# LabPower-PWM.net
KiCad netlist of a schematic drawn in EAGLE
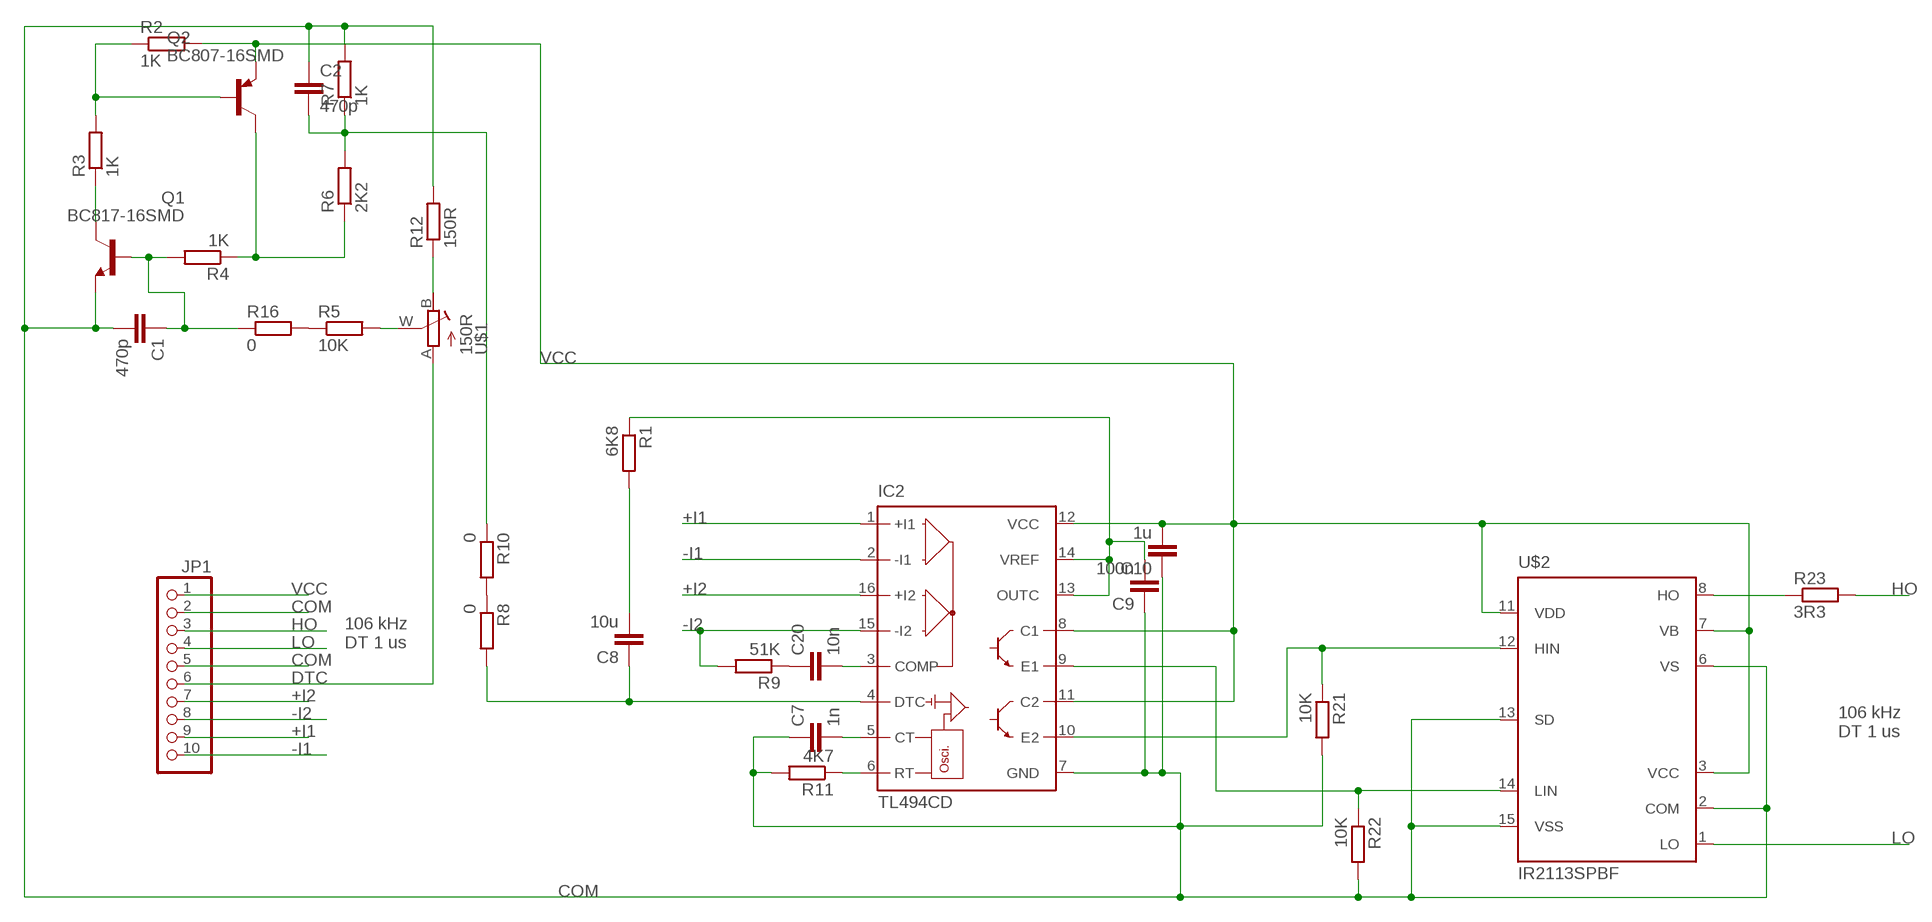
[diagram p0: schematic, sheet 1]

(export (version "E")
  (design (tool "Eeschema 10.0.6"))
  (components
    (comp (ref "C1")
      (value "470p")
      (footprint "eagle-import:C0805")
      (libsource (lib "eagle-import") (part "C-EUC0805"))
    )
    (comp (ref "C2")
      (value "470p")
      (footprint "eagle-import:C0805")
      (libsource (lib "eagle-import") (part "C-EUC0805"))
    )
    (comp (ref "C7")
      (value "1n")
      (footprint "eagle-import:C0805")
      (libsource (lib "eagle-import") (part "C-EUC0805"))
    )
    (comp (ref "C8")
      (value "10u")
      (footprint "eagle-import:C0805")
      (libsource (lib "eagle-import") (part "C-EUC0805"))
    )
    (comp (ref "C9")
      (value "100n")
      (footprint "eagle-import:C0805")
      (libsource (lib "eagle-import") (part "C-EUC0805"))
    )
    (comp (ref "C10")
      (value "1u")
      (footprint "eagle-import:C0805")
      (libsource (lib "eagle-import") (part "C-EUC0805"))
    )
    (comp (ref "C20")
      (value "10n")
      (footprint "eagle-import:C0805")
      (libsource (lib "eagle-import") (part "C-EUC0805"))
    )
    (comp (ref "IC2")
      (value "TL494CD")
      (footprint "eagle-import:SO16")
      (libsource (lib "eagle-import") (part "TL494DC"))
    )
    (comp (ref "JP1")
      (value "PINHD-1X10")
      (footprint "eagle-import:1X10")
      (libsource (lib "eagle-import") (part "PINHD-1X10"))
    )
    (comp (ref "Q1")
      (value "BC817-16SMD")
      (footprint "eagle-import:SOT23-BEC")
      (libsource (lib "eagle-import") (part "BC817SMD-16"))
    )
    (comp (ref "Q2")
      (value "BC807-16SMD")
      (footprint "eagle-import:SOT23-BEC")
      (libsource (lib "eagle-import") (part "BC807SMD-16"))
    )
    (comp (ref "R1")
      (value "6K8")
      (footprint "eagle-import:R0805")
      (libsource (lib "eagle-import") (part "R-EU_R0805"))
    )
    (comp (ref "R2")
      (value "1K")
      (footprint "eagle-import:R0805")
      (libsource (lib "eagle-import") (part "R-EU_R0805"))
    )
    (comp (ref "R3")
      (value "1K")
      (footprint "eagle-import:R0805")
      (libsource (lib "eagle-import") (part "R-EU_R0805"))
    )
    (comp (ref "R4")
      (value "1K")
      (footprint "eagle-import:R0805")
      (libsource (lib "eagle-import") (part "R-EU_R0805"))
    )
    (comp (ref "R5")
      (value "10K")
      (footprint "eagle-import:R0805")
      (libsource (lib "eagle-import") (part "R-EU_R0805"))
    )
    (comp (ref "R6")
      (value "2K2")
      (footprint "eagle-import:R0805")
      (libsource (lib "eagle-import") (part "R-EU_R0805"))
    )
    (comp (ref "R7")
      (value "1K")
      (footprint "eagle-import:R0805")
      (libsource (lib "eagle-import") (part "R-EU_R0805"))
    )
    (comp (ref "R8")
      (value "0")
      (footprint "eagle-import:R0805")
      (libsource (lib "eagle-import") (part "R-EU_R0805"))
    )
    (comp (ref "R9")
      (value "51K")
      (footprint "eagle-import:R0805")
      (libsource (lib "eagle-import") (part "R-EU_R0805"))
    )
    (comp (ref "R10")
      (value "0")
      (footprint "eagle-import:R0805")
      (libsource (lib "eagle-import") (part "R-EU_R0805"))
    )
    (comp (ref "R11")
      (value "4K7")
      (footprint "eagle-import:R0805")
      (libsource (lib "eagle-import") (part "R-EU_R0805"))
    )
    (comp (ref "R12")
      (value "150R")
      (footprint "eagle-import:R0805")
      (libsource (lib "eagle-import") (part "R-EU_R0805"))
    )
    (comp (ref "R16")
      (value "0")
      (footprint "eagle-import:R0805")
      (libsource (lib "eagle-import") (part "R-EU_R0805"))
    )
    (comp (ref "R21")
      (value "10K")
      (footprint "eagle-import:R0805")
      (libsource (lib "eagle-import") (part "R-EU_R0805"))
    )
    (comp (ref "R22")
      (value "10K")
      (footprint "eagle-import:R0805")
      (libsource (lib "eagle-import") (part "R-EU_R0805"))
    )
    (comp (ref "R23")
      (value "3R3")
      (footprint "eagle-import:R0805")
      (libsource (lib "eagle-import") (part "R-EU_R0805"))
    )
    (comp (ref "U$1")
      (value "150R")
      (footprint "eagle-import:RJ9W")
      (libsource (lib "eagle-import") (part "POTTURN-X"))
    )
    (comp (ref "U$2")
      (value "IR2113SPBF")
      (footprint "eagle-import:SO16W")
      (libsource (lib "eagle-import") (part "IR2113SPBF"))
    )
  )
  (nets
    (net (code "1") (name "/+I1") (class "Default")
      (node (ref "IC2") (pin "1") (pinfunction "+I1_1") (pintype "input"))
      (node (ref "JP1") (pin "9") (pinfunction "9_9") (pintype "passive"))
    )
    (net (code "2") (name "/+I2") (class "Default")
      (node (ref "IC2") (pin "16") (pinfunction "+I2_16") (pintype "input"))
      (node (ref "JP1") (pin "7") (pinfunction "7_7") (pintype "passive"))
    )
    (net (code "3") (name "/-I1") (class "Default")
      (node (ref "IC2") (pin "2") (pinfunction "-I1_2") (pintype "input"))
      (node (ref "JP1") (pin "10") (pinfunction "10_10") (pintype "passive"))
    )
    (net (code "4") (name "/-I2") (class "Default")
      (node (ref "IC2") (pin "15") (pinfunction "-I2_15") (pintype "input"))
      (node (ref "JP1") (pin "8") (pinfunction "8_8") (pintype "passive"))
      (node (ref "R9") (pin "2") (pinfunction "2_2") (pintype "passive"))
    )
    (net (code "5") (name "/COM") (class "Default")
      (node (ref "C1") (pin "2") (pinfunction "2_2") (pintype "passive"))
      (node (ref "C10") (pin "1") (pinfunction "1_1") (pintype "passive"))
      (node (ref "C2") (pin "1") (pinfunction "1_1") (pintype "passive"))
      (node (ref "C7") (pin "1") (pinfunction "1_1") (pintype "passive"))
      (node (ref "C9") (pin "1") (pinfunction "1_1") (pintype "passive"))
      (node (ref "IC2") (pin "7") (pinfunction "GND_7") (pintype "power_in"))
      (node (ref "JP1") (pin "2") (pinfunction "2_2") (pintype "passive"))
      (node (ref "JP1") (pin "5") (pinfunction "5_5") (pintype "passive"))
      (node (ref "Q1") (pin "E") (pinfunction "E_E") (pintype "passive"))
      (node (ref "R11") (pin "2") (pinfunction "2_2") (pintype "passive"))
      (node (ref "R12") (pin "2") (pinfunction "2_2") (pintype "passive"))
      (node (ref "R21") (pin "2") (pinfunction "2_2") (pintype "passive"))
      (node (ref "R22") (pin "2") (pinfunction "2_2") (pintype "passive"))
      (node (ref "R7") (pin "2") (pinfunction "2_2") (pintype "passive"))
      (node (ref "U$2") (pin "13") (pinfunction "SD_13") (pintype "input"))
      (node (ref "U$2") (pin "15") (pinfunction "VSS_15") (pintype "power_in"))
      (node (ref "U$2") (pin "2") (pinfunction "COM_2") (pintype "power_in"))
      (node (ref "U$2") (pin "6") (pinfunction "VS_6") (pintype "power_in"))
    )
    (net (code "6") (name "/DTC") (class "Default")
      (node (ref "JP1") (pin "6") (pinfunction "6_6") (pintype "passive"))
      (node (ref "U$1") (pin "A") (pinfunction "A_A") (pintype "passive"))
    )
    (net (code "7") (name "/HO") (class "Default")
      (node (ref "JP1") (pin "3") (pinfunction "3_3") (pintype "passive"))
      (node (ref "R23") (pin "2") (pinfunction "2_2") (pintype "passive"))
    )
    (net (code "8") (name "/LO") (class "Default")
      (node (ref "JP1") (pin "4") (pinfunction "4_4") (pintype "passive"))
      (node (ref "U$2") (pin "1") (pinfunction "LO_1") (pintype "output"))
    )
    (net (code "9") (name "/VCC") (class "Default")
      (node (ref "C10") (pin "2") (pinfunction "2_2") (pintype "passive"))
      (node (ref "IC2") (pin "11") (pinfunction "C2_11") (pintype "passive"))
      (node (ref "IC2") (pin "12") (pinfunction "VCC_12") (pintype "power_in"))
      (node (ref "IC2") (pin "8") (pinfunction "C1_8") (pintype "passive"))
      (node (ref "JP1") (pin "1") (pinfunction "1_1") (pintype "passive"))
      (node (ref "Q2") (pin "E") (pinfunction "E_E") (pintype "passive"))
      (node (ref "R2") (pin "2") (pinfunction "2_2") (pintype "passive"))
      (node (ref "U$2") (pin "11") (pinfunction "VDD_11") (pintype "power_in"))
      (node (ref "U$2") (pin "3") (pinfunction "VCC_3") (pintype "power_in"))
      (node (ref "U$2") (pin "7") (pinfunction "VB_7") (pintype "power_in"))
    )
    (net (code "10") (name "Net-(C1-Pad1)") (class "Default")
      (node (ref "C1") (pin "1") (pinfunction "1_1") (pintype "passive"))
      (node (ref "Q1") (pin "B") (pinfunction "B_B") (pintype "passive"))
      (node (ref "R16") (pin "1") (pinfunction "1_1") (pintype "passive"))
      (node (ref "R4") (pin "2") (pinfunction "2_2") (pintype "passive"))
    )
    (net (code "11") (name "Net-(C2-Pad2)") (class "Default")
      (node (ref "C2") (pin "2") (pinfunction "2_2") (pintype "passive"))
      (node (ref "R10") (pin "1") (pinfunction "1_1") (pintype "passive"))
      (node (ref "R6") (pin "2") (pinfunction "2_2") (pintype "passive"))
      (node (ref "R7") (pin "1") (pinfunction "1_1") (pintype "passive"))
    )
    (net (code "12") (name "Net-(C8-Pad2)") (class "Default")
      (node (ref "C8") (pin "2") (pinfunction "2_2") (pintype "passive"))
      (node (ref "R1") (pin "2") (pinfunction "2_2") (pintype "passive"))
    )
    (net (code "13") (name "Net-(C20-Pad1)") (class "Default")
      (node (ref "C20") (pin "1") (pinfunction "1_1") (pintype "passive"))
      (node (ref "R9") (pin "1") (pinfunction "1_1") (pintype "passive"))
    )
    (net (code "14") (name "Net-(IC2-COMP)") (class "Default")
      (node (ref "C20") (pin "2") (pinfunction "2_2") (pintype "passive"))
      (node (ref "IC2") (pin "3") (pinfunction "COMP_3") (pintype "passive"))
    )
    (net (code "15") (name "Net-(IC2-CT)") (class "Default")
      (node (ref "C7") (pin "2") (pinfunction "2_2") (pintype "passive"))
      (node (ref "IC2") (pin "5") (pinfunction "CT_5") (pintype "input"))
    )
    (net (code "16") (name "Net-(IC2-DTC)") (class "Default")
      (node (ref "C8") (pin "1") (pinfunction "1_1") (pintype "passive"))
      (node (ref "IC2") (pin "4") (pinfunction "DTC_4") (pintype "input"))
      (node (ref "R8") (pin "2") (pinfunction "2_2") (pintype "passive"))
    )
    (net (code "17") (name "Net-(IC2-E1)") (class "Default")
      (node (ref "IC2") (pin "9") (pinfunction "E1_9") (pintype "passive"))
      (node (ref "R22") (pin "1") (pinfunction "1_1") (pintype "passive"))
      (node (ref "U$2") (pin "14") (pinfunction "LIN_14") (pintype "input"))
    )
    (net (code "18") (name "Net-(IC2-E2)") (class "Default")
      (node (ref "IC2") (pin "10") (pinfunction "E2_10") (pintype "passive"))
      (node (ref "R21") (pin "1") (pinfunction "1_1") (pintype "passive"))
      (node (ref "U$2") (pin "12") (pinfunction "HIN_12") (pintype "input"))
    )
    (net (code "19") (name "Net-(IC2-OUTC)") (class "Default")
      (node (ref "C9") (pin "2") (pinfunction "2_2") (pintype "passive"))
      (node (ref "IC2") (pin "13") (pinfunction "OUTC_13") (pintype "output"))
      (node (ref "IC2") (pin "14") (pinfunction "VREF_14") (pintype "input"))
      (node (ref "R1") (pin "1") (pinfunction "1_1") (pintype "passive"))
    )
    (net (code "20") (name "Net-(IC2-RT)") (class "Default")
      (node (ref "IC2") (pin "6") (pinfunction "RT_6") (pintype "input"))
      (node (ref "R11") (pin "1") (pinfunction "1_1") (pintype "passive"))
    )
    (net (code "21") (name "Net-(Q1-PadC)") (class "Default")
      (node (ref "Q1") (pin "C") (pinfunction "C_C") (pintype "passive"))
      (node (ref "R3") (pin "1") (pinfunction "1_1") (pintype "passive"))
    )
    (net (code "22") (name "Net-(Q2-PadB)") (class "Default")
      (node (ref "Q2") (pin "B") (pinfunction "B_B") (pintype "passive"))
      (node (ref "R2") (pin "1") (pinfunction "1_1") (pintype "passive"))
      (node (ref "R3") (pin "2") (pinfunction "2_2") (pintype "passive"))
    )
    (net (code "23") (name "Net-(Q2-PadC)") (class "Default")
      (node (ref "Q2") (pin "C") (pinfunction "C_C") (pintype "passive"))
      (node (ref "R4") (pin "1") (pinfunction "1_1") (pintype "passive"))
      (node (ref "R6") (pin "1") (pinfunction "1_1") (pintype "passive"))
    )
    (net (code "24") (name "Net-(R10-Pad2)") (class "Default")
      (node (ref "R10") (pin "2") (pinfunction "2_2") (pintype "passive"))
      (node (ref "R8") (pin "1") (pinfunction "1_1") (pintype "passive"))
    )
    (net (code "25") (name "Net-(R16-Pad2)") (class "Default")
      (node (ref "R16") (pin "2") (pinfunction "2_2") (pintype "passive"))
      (node (ref "R5") (pin "1") (pinfunction "1_1") (pintype "passive"))
    )
    (net (code "26") (name "Net-(U$1-E)") (class "Default")
      (node (ref "R12") (pin "1") (pinfunction "1_1") (pintype "passive"))
      (node (ref "U$1") (pin "B") (pinfunction "E_B") (pintype "passive"))
    )
    (net (code "27") (name "Net-(U$1-S)") (class "Default")
      (node (ref "R5") (pin "2") (pinfunction "2_2") (pintype "passive"))
      (node (ref "U$1") (pin "W") (pinfunction "S_W") (pintype "passive"))
    )
    (net (code "28") (name "Net-(U$2-HO)") (class "Default")
      (node (ref "R23") (pin "1") (pinfunction "1_1") (pintype "passive"))
      (node (ref "U$2") (pin "8") (pinfunction "HO_8") (pintype "output"))
    )
  )
)
